# SparkX_smol_ARTIC_R2.net
KiCad netlist of a schematic drawn in EAGLE
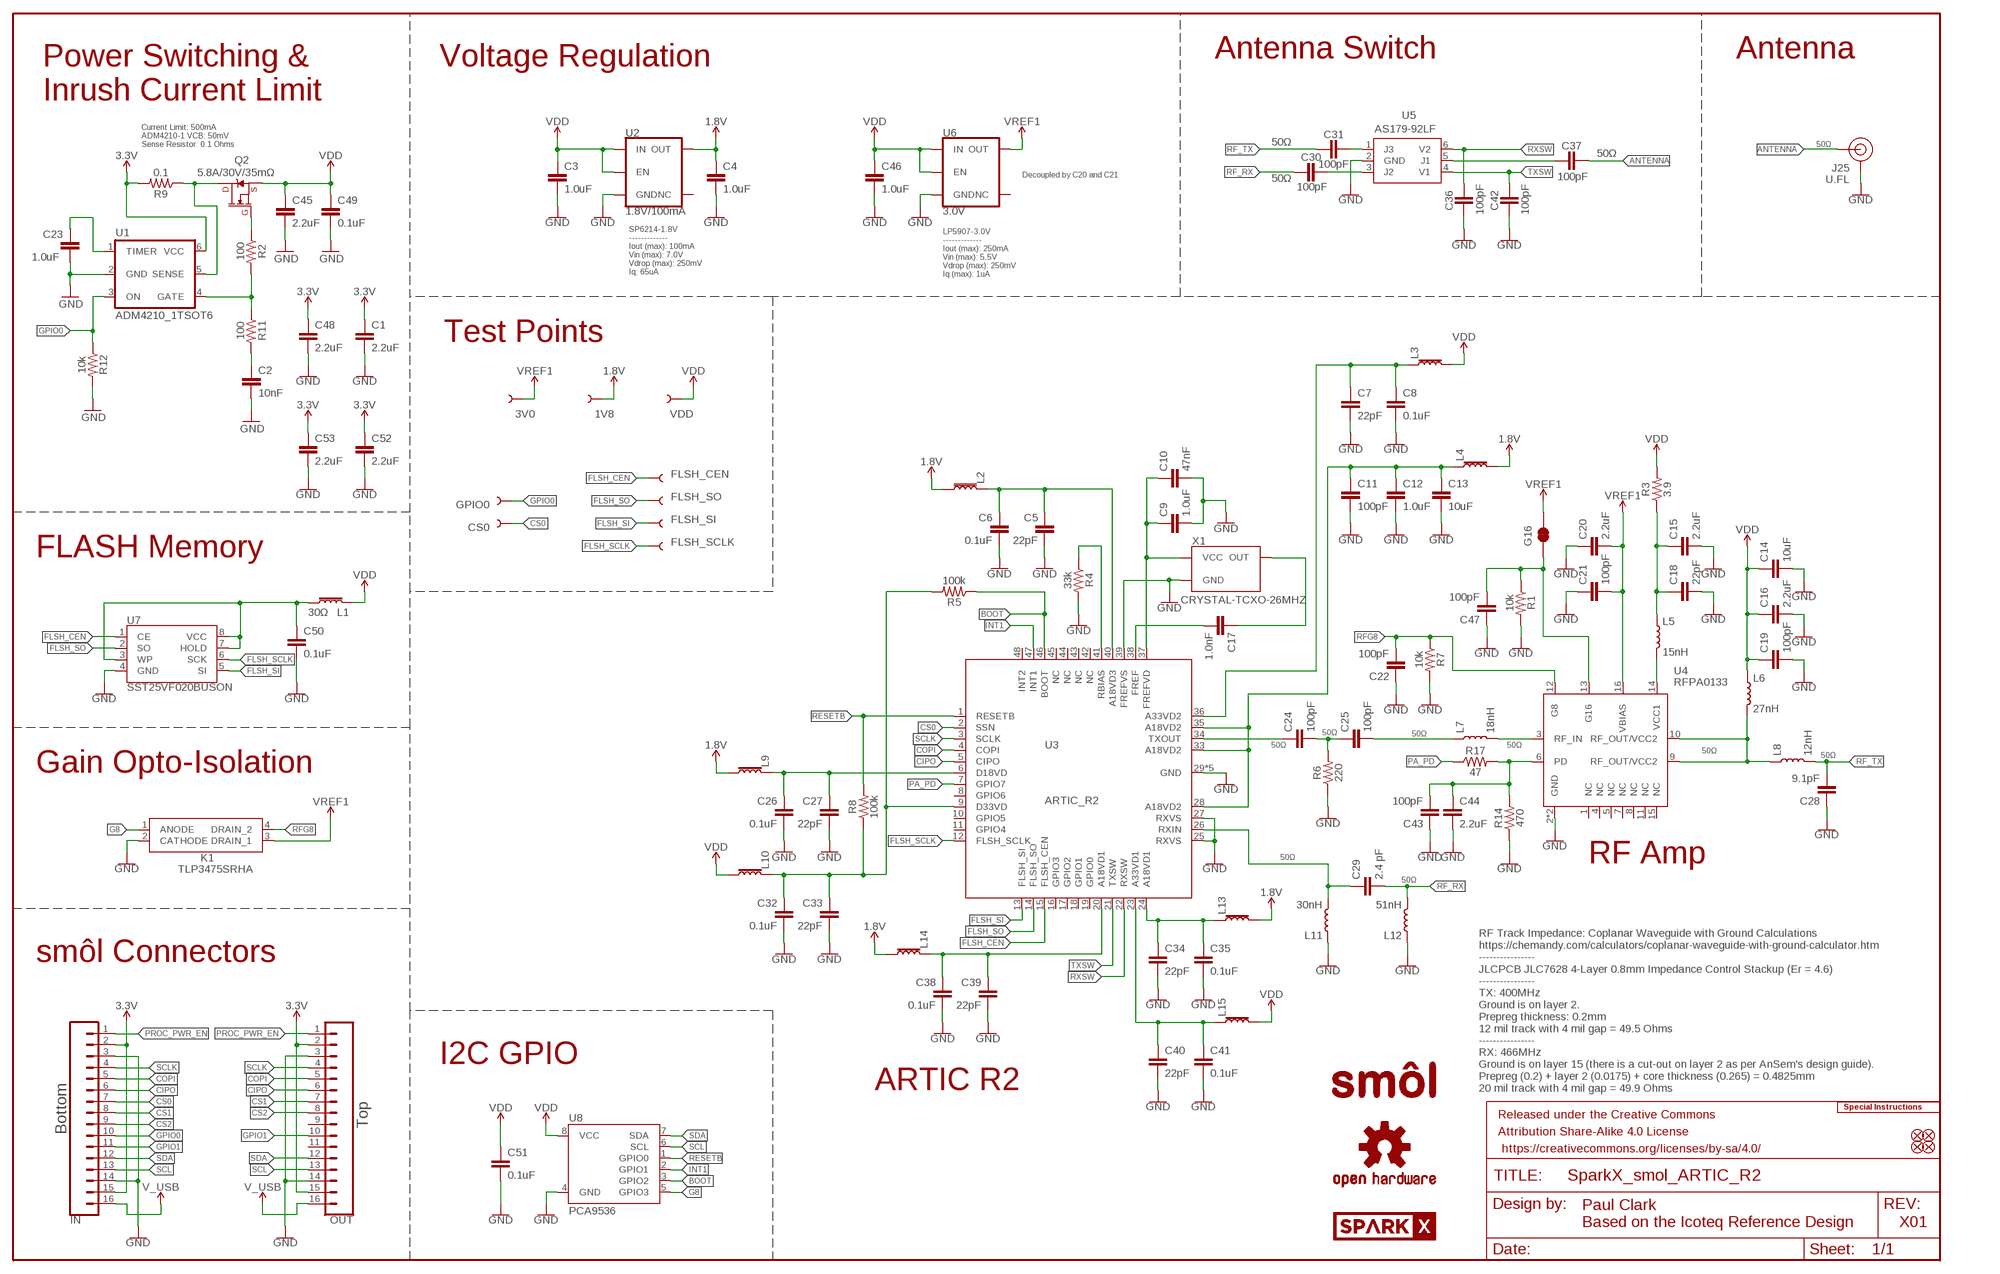
[diagram p0: schematic, sheet 1]

(export (version "E")
  (design (tool "Eeschema 10.0.6"))
  (components
    (comp (ref "1V8")
      (value "TEST-POINT3")
      (footprint "eagle-import:PAD.03X.03")
      (libsource (lib "eagle-import") (part "TEST-POINT3"))
    )
    (comp (ref "3V0")
      (value "TEST-POINT3")
      (footprint "eagle-import:PAD.03X.03")
      (libsource (lib "eagle-import") (part "TEST-POINT3"))
    )
    (comp (ref "C1")
      (value "2.2uF")
      (footprint "eagle-import:0402-TIGHT")
      (libsource (lib "eagle-import") (part "2.2UF-0402_TIGHT-10V-10%-X5R"))
    )
    (comp (ref "C2")
      (value "10nF")
      (footprint "eagle-import:0402-TIGHT")
      (libsource (lib "eagle-import") (part "10NF-0402T-25V-10%"))
    )
    (comp (ref "C3")
      (value "1.0uF")
      (footprint "eagle-import:0402-TIGHT")
      (libsource (lib "eagle-import") (part "1.0UF-0402T-16V-10%"))
    )
    (comp (ref "C4")
      (value "1.0uF")
      (footprint "eagle-import:0402-TIGHT")
      (libsource (lib "eagle-import") (part "1.0UF-0402T-16V-10%"))
    )
    (comp (ref "C5")
      (value "22pF")
      (footprint "eagle-import:0402-TIGHT")
      (libsource (lib "eagle-import") (part "22PF-0402T-16V-10%"))
    )
    (comp (ref "C6")
      (value "0.1uF")
      (footprint "eagle-import:0402-TIGHT")
      (libsource (lib "eagle-import") (part "0.1UF-0402T-6.3V-10%-X7R"))
    )
    (comp (ref "C7")
      (value "22pF")
      (footprint "eagle-import:0402-TIGHT")
      (libsource (lib "eagle-import") (part "22PF-0402T-16V-10%"))
    )
    (comp (ref "C8")
      (value "0.1uF")
      (footprint "eagle-import:0402-TIGHT")
      (libsource (lib "eagle-import") (part "0.1UF-0402T-6.3V-10%-X7R"))
    )
    (comp (ref "C9")
      (value "1.0uF")
      (footprint "eagle-import:0402-TIGHT")
      (libsource (lib "eagle-import") (part "1.0UF-0402T-16V-10%"))
    )
    (comp (ref "C10")
      (value "47nF")
      (footprint "eagle-import:0402-TIGHT")
      (libsource (lib "eagle-import") (part "47NF-0402_TIGHT-25V-10%-X7R"))
    )
    (comp (ref "C11")
      (value "100pF")
      (footprint "eagle-import:0402-TIGHT")
      (libsource (lib "eagle-import") (part "100PF-0402T-50V-5%"))
    )
    (comp (ref "C12")
      (value "1.0uF")
      (footprint "eagle-import:0402-TIGHT")
      (libsource (lib "eagle-import") (part "1.0UF-0402T-16V-10%"))
    )
    (comp (ref "C13")
      (value "10uF")
      (footprint "eagle-import:0402-TIGHT")
      (libsource (lib "eagle-import") (part "10UF-0402T-6.3V-20%"))
    )
    (comp (ref "C14")
      (value "10uF")
      (footprint "eagle-import:0402-TIGHT")
      (libsource (lib "eagle-import") (part "10UF-0402T-6.3V-20%"))
    )
    (comp (ref "C15")
      (value "2.2uF")
      (footprint "eagle-import:0402-TIGHT")
      (libsource (lib "eagle-import") (part "2.2UF-0402_TIGHT-10V-10%-X5R"))
    )
    (comp (ref "C16")
      (value "2.2uF")
      (footprint "eagle-import:0402-TIGHT")
      (libsource (lib "eagle-import") (part "2.2UF-0402_TIGHT-10V-10%-X5R"))
    )
    (comp (ref "C17")
      (value "1.0nF")
      (footprint "eagle-import:0402-TIGHT")
      (libsource (lib "eagle-import") (part "1.0NF/1000PF-0402_TIGHT-50V-10%"))
    )
    (comp (ref "C18")
      (value "22pF")
      (footprint "eagle-import:0402-TIGHT")
      (libsource (lib "eagle-import") (part "22PF-0402T-16V-10%"))
    )
    (comp (ref "C19")
      (value "100pF")
      (footprint "eagle-import:0402-TIGHT")
      (libsource (lib "eagle-import") (part "100PF-0402T-50V-5%"))
    )
    (comp (ref "C20")
      (value "2.2uF")
      (footprint "eagle-import:0402-TIGHT")
      (libsource (lib "eagle-import") (part "2.2UF-0402_TIGHT-10V-10%-X5R"))
    )
    (comp (ref "C21")
      (value "100pF")
      (footprint "eagle-import:0402-TIGHT")
      (libsource (lib "eagle-import") (part "100PF-0402T-50V-5%"))
    )
    (comp (ref "C22")
      (value "100pF")
      (footprint "eagle-import:0402-TIGHT")
      (libsource (lib "eagle-import") (part "100PF-0402T-50V-5%"))
    )
    (comp (ref "C23")
      (value "1.0uF")
      (footprint "eagle-import:0402-TIGHT")
      (libsource (lib "eagle-import") (part "1.0UF-0402T-16V-10%"))
    )
    (comp (ref "C24")
      (value "100pF")
      (footprint "eagle-import:0402-TIGHT")
      (libsource (lib "eagle-import") (part "100PF-0402T-50V-5%"))
    )
    (comp (ref "C25")
      (value "100pF")
      (footprint "eagle-import:0402-TIGHT")
      (libsource (lib "eagle-import") (part "100PF-0402T-50V-5%"))
    )
    (comp (ref "C26")
      (value "0.1uF")
      (footprint "eagle-import:0402-TIGHT")
      (libsource (lib "eagle-import") (part "0.1UF-0402T-6.3V-10%-X7R"))
    )
    (comp (ref "C27")
      (value "22pF")
      (footprint "eagle-import:0402-TIGHT")
      (libsource (lib "eagle-import") (part "22PF-0402T-16V-10%"))
    )
    (comp (ref "C28")
      (value "9.1pF")
      (footprint "eagle-import:0402-TIGHT")
      (fields (field (name "MOUSER_PART") "609-500R07S9R1CV4T"))
      (libsource (lib "eagle-import") (part "9.1PF-0402-TIGHT"))
    )
    (comp (ref "C29")
      (value "2.4 pF")
      (footprint "eagle-import:0402_MURATA")
      (libsource (lib "eagle-import") (part "2.4PF-0402"))
    )
    (comp (ref "C30")
      (value "100pF")
      (footprint "eagle-import:0402-TIGHT")
      (libsource (lib "eagle-import") (part "100PF-0402T-50V-5%"))
    )
    (comp (ref "C31")
      (value "100pF")
      (footprint "eagle-import:0402-TIGHT")
      (libsource (lib "eagle-import") (part "100PF-0402T-50V-5%"))
    )
    (comp (ref "C32")
      (value "0.1uF")
      (footprint "eagle-import:0402-TIGHT")
      (libsource (lib "eagle-import") (part "0.1UF-0402T-6.3V-10%-X7R"))
    )
    (comp (ref "C33")
      (value "22pF")
      (footprint "eagle-import:0402-TIGHT")
      (libsource (lib "eagle-import") (part "22PF-0402T-16V-10%"))
    )
    (comp (ref "C34")
      (value "22pF")
      (footprint "eagle-import:0402-TIGHT")
      (libsource (lib "eagle-import") (part "22PF-0402T-16V-10%"))
    )
    (comp (ref "C35")
      (value "0.1uF")
      (footprint "eagle-import:0402-TIGHT")
      (libsource (lib "eagle-import") (part "0.1UF-0402T-6.3V-10%-X7R"))
    )
    (comp (ref "C36")
      (value "100pF")
      (footprint "eagle-import:0402-TIGHT")
      (libsource (lib "eagle-import") (part "100PF-0402T-50V-5%"))
    )
    (comp (ref "C37")
      (value "100pF")
      (footprint "eagle-import:0402-TIGHT")
      (libsource (lib "eagle-import") (part "100PF-0402T-50V-5%"))
    )
    (comp (ref "C38")
      (value "0.1uF")
      (footprint "eagle-import:0402-TIGHT")
      (libsource (lib "eagle-import") (part "0.1UF-0402T-6.3V-10%-X7R"))
    )
    (comp (ref "C39")
      (value "22pF")
      (footprint "eagle-import:0402-TIGHT")
      (libsource (lib "eagle-import") (part "22PF-0402T-16V-10%"))
    )
    (comp (ref "C40")
      (value "22pF")
      (footprint "eagle-import:0402-TIGHT")
      (libsource (lib "eagle-import") (part "22PF-0402T-16V-10%"))
    )
    (comp (ref "C41")
      (value "0.1uF")
      (footprint "eagle-import:0402-TIGHT")
      (libsource (lib "eagle-import") (part "0.1UF-0402T-6.3V-10%-X7R"))
    )
    (comp (ref "C42")
      (value "100pF")
      (footprint "eagle-import:0402-TIGHT")
      (libsource (lib "eagle-import") (part "100PF-0402T-50V-5%"))
    )
    (comp (ref "C43")
      (value "100pF")
      (footprint "eagle-import:0402-TIGHT")
      (libsource (lib "eagle-import") (part "100PF-0402T-50V-5%"))
    )
    (comp (ref "C44")
      (value "2.2uF")
      (footprint "eagle-import:0402-TIGHT")
      (libsource (lib "eagle-import") (part "2.2UF-0402_TIGHT-10V-10%-X5R"))
    )
    (comp (ref "C45")
      (value "2.2uF")
      (footprint "eagle-import:0402-TIGHT")
      (libsource (lib "eagle-import") (part "2.2UF-0402_TIGHT-10V-10%-X5R"))
    )
    (comp (ref "C46")
      (value "1.0uF")
      (footprint "eagle-import:0402-TIGHT")
      (libsource (lib "eagle-import") (part "1.0UF-0402T-16V-10%"))
    )
    (comp (ref "C47")
      (value "100pF")
      (footprint "eagle-import:0402-TIGHT")
      (libsource (lib "eagle-import") (part "100PF-0402T-50V-5%"))
    )
    (comp (ref "C48")
      (value "2.2uF")
      (footprint "eagle-import:0402-TIGHT")
      (libsource (lib "eagle-import") (part "2.2UF-0402_TIGHT-10V-10%-X5R"))
    )
    (comp (ref "C49")
      (value "0.1uF")
      (footprint "eagle-import:0402-TIGHT")
      (libsource (lib "eagle-import") (part "0.1UF-0402T-10V-10%-X7R"))
    )
    (comp (ref "C50")
      (value "0.1uF")
      (footprint "eagle-import:0402-TIGHT")
      (libsource (lib "eagle-import") (part "0.1UF-0402T-6.3V-10%-X7R"))
    )
    (comp (ref "C51")
      (value "0.1uF")
      (footprint "eagle-import:0402-TIGHT")
      (libsource (lib "eagle-import") (part "0.1UF-0402T-10V-10%-X7R"))
    )
    (comp (ref "C52")
      (value "2.2uF")
      (footprint "eagle-import:0402-TIGHT")
      (libsource (lib "eagle-import") (part "2.2UF-0402_TIGHT-10V-10%-X5R"))
    )
    (comp (ref "C53")
      (value "2.2uF")
      (footprint "eagle-import:0402-TIGHT")
      (libsource (lib "eagle-import") (part "2.2UF-0402_TIGHT-10V-10%-X5R"))
    )
    (comp (ref "CS0")
      (value "TEST-POINT3")
      (footprint "eagle-import:PAD.03X.03")
      (libsource (lib "eagle-import") (part "TEST-POINT3"))
    )
    (comp (ref "FD1")
      (value "FIDUCIALUFIDUCIAL")
      (footprint "eagle-import:FIDUCIAL-MICRO")
      (libsource (lib "eagle-import") (part "FIDUCIALUFIDUCIAL"))
    )
    (comp (ref "FD2")
      (value "FIDUCIALUFIDUCIAL")
      (footprint "eagle-import:FIDUCIAL-MICRO")
      (libsource (lib "eagle-import") (part "FIDUCIALUFIDUCIAL"))
    )
    (comp (ref "FD3")
      (value "FIDUCIALUFIDUCIAL")
      (footprint "eagle-import:FIDUCIAL-MICRO")
      (libsource (lib "eagle-import") (part "FIDUCIALUFIDUCIAL"))
    )
    (comp (ref "FD4")
      (value "FIDUCIALUFIDUCIAL")
      (footprint "eagle-import:FIDUCIAL-MICRO")
      (libsource (lib "eagle-import") (part "FIDUCIALUFIDUCIAL"))
    )
    (comp (ref "FLSH_CEN")
      (value "TEST-POINT3")
      (footprint "eagle-import:PAD.03X.03")
      (libsource (lib "eagle-import") (part "TEST-POINT3"))
    )
    (comp (ref "FLSH_SCLK")
      (value "TEST-POINT3")
      (footprint "eagle-import:PAD.03X.03")
      (libsource (lib "eagle-import") (part "TEST-POINT3"))
    )
    (comp (ref "FLSH_SI")
      (value "TEST-POINT3")
      (footprint "eagle-import:PAD.03X.03")
      (libsource (lib "eagle-import") (part "TEST-POINT3"))
    )
    (comp (ref "FLSH_SO")
      (value "TEST-POINT3")
      (footprint "eagle-import:PAD.03X.03")
      (libsource (lib "eagle-import") (part "TEST-POINT3"))
    )
    (comp (ref "FRAME1")
      (value "FRAME-LEDGER")
      (footprint "eagle-import:CREATIVE_COMMONS")
      (libsource (lib "eagle-import") (part "FRAME-LEDGER"))
    )
    (comp (ref "G16")
      (value "JUMPER-SMT_2_NC_TRACE_NO-SILK")
      (footprint "eagle-import:SMT-JUMPER_2_NC_TRACE_NO-SILK")
      (libsource (lib "eagle-import") (part "JUMPER-SMT_2_NC_TRACE_NO-SILK"))
    )
    (comp (ref "GPIO0")
      (value "TEST-POINT3")
      (footprint "eagle-import:PAD.03X.03")
      (libsource (lib "eagle-import") (part "TEST-POINT3"))
    )
    (comp (ref "IN")
      (value "CONN_16FPC_16_0.5MM")
      (footprint "eagle-import:FPC_16_0.5MM")
      (libsource (lib "eagle-import") (part "CONN_16FPC_16_0.5MM"))
    )
    (comp (ref "J25")
      (value "U.FL")
      (footprint "eagle-import:U.FL_REDUCED_FOOTPRINT")
      (libsource (lib "eagle-import") (part "U.FL2PIN-REDUCED-FOOTPRINT"))
    )
    (comp (ref "K1")
      (value "TLP3475SRHA")
      (footprint "eagle-import:TLP3475SRHA")
      (fields (field (name "DIGIKEY_PART") "264-TLP3475SRHA(TPECT-ND - Cut Tape (CT)"))
      (libsource (lib "eagle-import") (part "TLP3475SRHA"))
    )
    (comp (ref "L1")
      (value "30Ω")
      (footprint "eagle-import:0402-TIGHT")
      (libsource (lib "eagle-import") (part "FERRITE_BEAD-0402-30Ω-100MHZ"))
    )
    (comp (ref "L2")
      (value "30Ω")
      (footprint "eagle-import:0402-TIGHT")
      (libsource (lib "eagle-import") (part "FERRITE_BEAD-0402-30Ω-100MHZ"))
    )
    (comp (ref "L3")
      (value "30Ω")
      (footprint "eagle-import:0402-TIGHT")
      (libsource (lib "eagle-import") (part "FERRITE_BEAD-0402-30Ω-100MHZ"))
    )
    (comp (ref "L4")
      (value "30Ω")
      (footprint "eagle-import:0402-TIGHT")
      (libsource (lib "eagle-import") (part "FERRITE_BEAD-0402-30Ω-100MHZ"))
    )
    (comp (ref "L5")
      (value "15nH")
      (footprint "eagle-import:0402_COILCRAFT")
      (fields (field (name "MOUSER_PART") "994-0402HP-15NXGLU"))
      (libsource (lib "eagle-import") (part "15NH-0402"))
    )
    (comp (ref "L6")
      (value "27nH")
      (footprint "eagle-import:0402_COILCRAFT")
      (fields (field (name "MOUSER_PART") "994-0402HP-27NXGLU"))
      (libsource (lib "eagle-import") (part "27NH-0402"))
    )
    (comp (ref "L7")
      (value "18nH")
      (footprint "eagle-import:0402_COILCRAFT")
      (fields (field (name "MOUSER_PART") "994-0402HP-18NXGLU"))
      (libsource (lib "eagle-import") (part "18NH-0402"))
    )
    (comp (ref "L8")
      (value "12nH")
      (footprint "eagle-import:0402_COILCRAFT")
      (fields (field (name "MOUSER_PART") "994-0402HP-12NXGLU"))
      (libsource (lib "eagle-import") (part "12NH-0402"))
    )
    (comp (ref "L9")
      (value "30Ω")
      (footprint "eagle-import:0402-TIGHT")
      (libsource (lib "eagle-import") (part "FERRITE_BEAD-0402-30Ω-100MHZ"))
    )
    (comp (ref "L10")
      (value "30Ω")
      (footprint "eagle-import:0402-TIGHT")
      (libsource (lib "eagle-import") (part "FERRITE_BEAD-0402-30Ω-100MHZ"))
    )
    (comp (ref "L11")
      (value "30nH")
      (footprint "eagle-import:0402_COILCRAFT")
      (fields (field (name "MOUSER_PART") "994-0402HP-30NXGLU"))
      (libsource (lib "eagle-import") (part "30NH-0402"))
    )
    (comp (ref "L12")
      (value "51nH")
      (footprint "eagle-import:0402_COILCRAFT")
      (fields (field (name "MOUSER_PART") "994-0402HP-51NXGLU"))
      (libsource (lib "eagle-import") (part "51NH-0402"))
    )
    (comp (ref "L13")
      (value "30Ω")
      (footprint "eagle-import:0402-TIGHT")
      (libsource (lib "eagle-import") (part "FERRITE_BEAD-0402-30Ω-100MHZ"))
    )
    (comp (ref "L14")
      (value "30Ω")
      (footprint "eagle-import:0402-TIGHT")
      (libsource (lib "eagle-import") (part "FERRITE_BEAD-0402-30Ω-100MHZ"))
    )
    (comp (ref "L15")
      (value "30Ω")
      (footprint "eagle-import:0402-TIGHT")
      (libsource (lib "eagle-import") (part "FERRITE_BEAD-0402-30Ω-100MHZ"))
    )
    (comp (ref "LOGO1")
      (value "SPECIAL_INSTRUCTIONS-ORDERING")
      (footprint "eagle-import:ORDERING_INSTRUCTIONS")
      (libsource (lib "eagle-import") (part "SPECIAL_INSTRUCTIONS-ORDERING"))
    )
    (comp (ref "LOGO2")
      (value "OSHW-LOGOMINI")
      (footprint "eagle-import:OSHW-LOGO-MINI")
      (libsource (lib "eagle-import") (part "OSHW-LOGOMINI"))
    )
    (comp (ref "LOGO3")
      (value "OSHW-LOGOMINI")
      (footprint "eagle-import:OSHW-LOGO-MINI")
      (libsource (lib "eagle-import") (part "OSHW-LOGOMINI"))
    )
    (comp (ref "OUT")
      (value "CONN_16FPC_16_0.5MM")
      (footprint "eagle-import:FPC_16_0.5MM")
      (libsource (lib "eagle-import") (part "CONN_16FPC_16_0.5MM"))
    )
    (comp (ref "Q2")
      (value "5.8A/30V/35mΩ")
      (footprint "eagle-import:SOT23-3")
      (libsource (lib "eagle-import") (part "MOSFET-NCH-AO3404A"))
    )
    (comp (ref "R1")
      (value "10k")
      (footprint "eagle-import:0402-TIGHT")
      (libsource (lib "eagle-import") (part "10KOHM-0402T-1/16W-1%"))
    )
    (comp (ref "R2")
      (value "100")
      (footprint "eagle-import:0402-TIGHT")
      (libsource (lib "eagle-import") (part "100OHM-0402-TIGHT-1/16W-1%"))
    )
    (comp (ref "R3")
      (value "3.9")
      (footprint "eagle-import:0402-TIGHT")
      (libsource (lib "eagle-import") (part "3.9OHM-0402-TIGHT-1/16W-1%"))
    )
    (comp (ref "R4")
      (value "33k")
      (footprint "eagle-import:0402-TIGHT")
      (libsource (lib "eagle-import") (part "33KOHM-0402T-1/16W-1%"))
    )
    (comp (ref "R5")
      (value "100k")
      (footprint "eagle-import:0402-TIGHT")
      (libsource (lib "eagle-import") (part "100KOHM-0402T-1/16W-1%"))
    )
    (comp (ref "R6")
      (value "220")
      (footprint "eagle-import:0402-TIGHT")
      (libsource (lib "eagle-import") (part "220OHM-0402-TIGHT-1/16W-1%"))
    )
    (comp (ref "R7")
      (value "10k")
      (footprint "eagle-import:0402-TIGHT")
      (libsource (lib "eagle-import") (part "10KOHM-0402T-1/16W-1%"))
    )
    (comp (ref "R8")
      (value "100k")
      (footprint "eagle-import:0402-TIGHT")
      (libsource (lib "eagle-import") (part "100KOHM-0402T-1/16W-1%"))
    )
    (comp (ref "R9")
      (value "0.1")
      (footprint "eagle-import:0603")
      (libsource (lib "eagle-import") (part "0.1OHM-0603-1/3W-1%"))
    )
    (comp (ref "R11")
      (value "100")
      (footprint "eagle-import:0402-TIGHT")
      (libsource (lib "eagle-import") (part "100OHM-0402-TIGHT-1/16W-1%"))
    )
    (comp (ref "R12")
      (value "10k")
      (footprint "eagle-import:0402-TIGHT")
      (libsource (lib "eagle-import") (part "10KOHM-0402T-1/16W-1%"))
    )
    (comp (ref "R14")
      (value "470")
      (footprint "eagle-import:0402-TIGHT")
      (libsource (lib "eagle-import") (part "470OHM-0402-TIGHT-1/16W-1%"))
    )
    (comp (ref "R17")
      (value "47")
      (footprint "eagle-import:0402-TIGHT")
      (libsource (lib "eagle-import") (part "47OHM-0402-TIGHT-1/16W-1%"))
    )
    (comp (ref "U$2")
      (value "SMOL_LOGOSMALL")
      (footprint "eagle-import:SMOL_SMALL")
      (libsource (lib "eagle-import") (part "SMOL_LOGOSMALL"))
    )
    (comp (ref "U$3")
      (value "SMOL_LOGOSMALL")
      (footprint "eagle-import:SMOL_SMALL")
      (libsource (lib "eagle-import") (part "SMOL_LOGOSMALL"))
    )
    (comp (ref "U$4")
      (value "SPARKX-LOGO3")
      (footprint "eagle-import:SPARKX-SMALL")
      (libsource (lib "eagle-import") (part "SPARKX-LOGO3"))
    )
    (comp (ref "U$8")
      (value "SPARKX-LOGO2")
      (footprint "eagle-import:SPARKX-TINY")
      (libsource (lib "eagle-import") (part "SPARKX-LOGO2"))
    )
    (comp (ref "U1")
      (value "ADM4210_1TSOT6")
      (footprint "eagle-import:TSOT6")
      (libsource (lib "eagle-import") (part "ADM4210_1TSOT6"))
    )
    (comp (ref "U2")
      (value "1.8V/100mA")
      (footprint "eagle-import:SC70")
      (libsource (lib "eagle-import") (part "V_REG_SP6214-1.8V"))
    )
    (comp (ref "U3")
      (value "ARTIC_R2")
      (footprint "eagle-import:QFN-48")
      (libsource (lib "eagle-import") (part "ARTIC_R2"))
    )
    (comp (ref "U4")
      (value "RFPA0133")
      (footprint "eagle-import:QFN50P300X300X86-17N")
      (fields
        (field (name "MANUFACTURER_PART_NUMBER") "RFPA0133TR7")
        (field (name "MOUSER_PART_NUMBER") "772-RFPA0133")
      )
      (libsource (lib "eagle-import") (part "RFPA0133"))
    )
    (comp (ref "U5")
      (value "AS179-92LF")
      (footprint "eagle-import:SOT65P220X100-6N")
      (libsource (lib "eagle-import") (part "AS179-92LF"))
    )
    (comp (ref "U6")
      (value "3.0V")
      (footprint "eagle-import:SOT23-5")
      (fields
        (field (name "DIGIKEY_PART") "296-40357-1-ND")
        (field (name "MANU_PART") "LP5907MFX-3.0/NOPB")
        (field (name "MOUSER_PART") "595-LP5907MFX-3.0NPB")
      )
      (libsource (lib "eagle-import") (part "V_REG_LP5907SOT23-3.0V"))
    )
    (comp (ref "U7")
      (value "SST25VF020BUSON")
      (footprint "eagle-import:USON_3X2MM")
      (fields
        (field (name "DIGIKEY_PART") "SST25VF020B-80-4I-Q3AE-TCT-ND")
        (field (name "MANU_PART") "SST25VF020B-80-4I-Q3AE-T")
      )
      (libsource (lib "eagle-import") (part "SST25VF020BUSON"))
    )
    (comp (ref "U8")
      (value "PCA9536")
      (footprint "eagle-import:MSOP8")
      (libsource (lib "eagle-import") (part "PCA9536"))
    )
    (comp (ref "VDD")
      (value "TEST-POINT3")
      (footprint "eagle-import:PAD.03X.03")
      (libsource (lib "eagle-import") (part "TEST-POINT3"))
    )
    (comp (ref "X1")
      (value "CRYSTAL-TCXO-26MHZ")
      (footprint "eagle-import:CRYSTAL-TCXO-SMD-1.65X1.25")
      (fields (field (name "MOUSER_PART") "449-LFTCXO073004CUTT"))
      (libsource (lib "eagle-import") (part "CRYSTAL-TCXO-26MHZ"))
    )
  )
  (nets
    (net (code "1") (name "1.8V") (class "Default")
      (node (ref "1V8") (pin "1") (pinfunction "1_1") (pintype "bidirectional"))
      (node (ref "C4") (pin "1") (pinfunction "1_1") (pintype "passive"))
      (node (ref "L13") (pin "2") (pinfunction "2_2") (pintype "passive"))
      (node (ref "L14") (pin "2") (pinfunction "2_2") (pintype "passive"))
      (node (ref "L2") (pin "2") (pinfunction "2_2") (pintype "passive"))
      (node (ref "L4") (pin "2") (pinfunction "2_2") (pintype "passive"))
      (node (ref "L9") (pin "2") (pinfunction "2_2") (pintype "passive"))
      (node (ref "U2") (pin "5") (pinfunction "OUT_5") (pintype "passive"))
    )
    (net (code "2") (name "3.3V") (class "Default")
      (node (ref "C1") (pin "1") (pinfunction "1_1") (pintype "passive"))
      (node (ref "C48") (pin "1") (pinfunction "1_1") (pintype "passive"))
      (node (ref "C52") (pin "1") (pinfunction "1_1") (pintype "passive"))
      (node (ref "C53") (pin "1") (pinfunction "1_1") (pintype "passive"))
      (node (ref "IN") (pin "15") (pinfunction "15_15") (pintype "passive"))
      (node (ref "IN") (pin "2") (pinfunction "2_2") (pintype "passive"))
      (node (ref "OUT") (pin "15") (pinfunction "15_15") (pintype "passive"))
      (node (ref "OUT") (pin "2") (pinfunction "2_2") (pintype "passive"))
      (node (ref "R9") (pin "2") (pinfunction "2_2") (pintype "passive"))
      (node (ref "U1") (pin "6") (pinfunction "VCC_6") (pintype "power_in"))
    )
    (net (code "3") (name "ANTENNA") (class "Default")
      (node (ref "C37") (pin "1") (pinfunction "1_1") (pintype "passive"))
      (node (ref "J25") (pin "FEED") (pinfunction "SIGNAL_FEED") (pintype "bidirectional"))
    )
    (net (code "4") (name "BOOT") (class "Default")
      (node (ref "R5") (pin "1") (pinfunction "1_1") (pintype "passive"))
      (node (ref "U3") (pin "46") (pinfunction "BOOT_46") (pintype "bidirectional"))
      (node (ref "U8") (pin "3") (pinfunction "GPIO2_3") (pintype "bidirectional"))
    )
    (net (code "5") (name "CIPO") (class "Default")
      (node (ref "IN") (pin "6") (pinfunction "6_6") (pintype "passive"))
      (node (ref "OUT") (pin "6") (pinfunction "6_6") (pintype "passive"))
      (node (ref "U3") (pin "5") (pinfunction "CIPO_5") (pintype "bidirectional"))
    )
    (net (code "6") (name "COPI") (class "Default")
      (node (ref "IN") (pin "5") (pinfunction "5_5") (pintype "passive"))
      (node (ref "OUT") (pin "5") (pinfunction "5_5") (pintype "passive"))
      (node (ref "U3") (pin "4") (pinfunction "COPI_4") (pintype "bidirectional"))
    )
    (net (code "7") (name "CS0") (class "Default")
      (node (ref "CS0") (pin "1") (pinfunction "1_1") (pintype "bidirectional"))
      (node (ref "IN") (pin "7") (pinfunction "7_7") (pintype "passive"))
      (node (ref "U3") (pin "2") (pinfunction "SSN_2") (pintype "bidirectional"))
    )
    (net (code "8") (name "CS1") (class "Default")
      (node (ref "IN") (pin "8") (pinfunction "8_8") (pintype "passive"))
      (node (ref "OUT") (pin "7") (pinfunction "7_7") (pintype "passive"))
    )
    (net (code "9") (name "CS2") (class "Default")
      (node (ref "IN") (pin "9") (pinfunction "9_9") (pintype "passive"))
      (node (ref "OUT") (pin "8") (pinfunction "8_8") (pintype "passive"))
    )
    (net (code "10") (name "FLSH_CEN") (class "Default")
      (node (ref "FLSH_CEN") (pin "1") (pinfunction "1_1") (pintype "bidirectional"))
      (node (ref "U3") (pin "15") (pinfunction "FLSH_CEN_15") (pintype "bidirectional"))
      (node (ref "U7") (pin "1") (pinfunction "CE_1") (pintype "bidirectional"))
    )
    (net (code "11") (name "FLSH_SCLK") (class "Default")
      (node (ref "FLSH_SCLK") (pin "1") (pinfunction "1_1") (pintype "bidirectional"))
      (node (ref "U3") (pin "12") (pinfunction "FLSH_SCLK_12") (pintype "bidirectional"))
      (node (ref "U7") (pin "6") (pinfunction "SCK_6") (pintype "bidirectional"))
    )
    (net (code "12") (name "FLSH_SI") (class "Default")
      (node (ref "FLSH_SI") (pin "1") (pinfunction "1_1") (pintype "bidirectional"))
      (node (ref "U3") (pin "13") (pinfunction "FLSH_SI_13") (pintype "bidirectional"))
      (node (ref "U7") (pin "5") (pinfunction "SI_5") (pintype "bidirectional"))
    )
    (net (code "13") (name "FLSH_SO") (class "Default")
      (node (ref "FLSH_SO") (pin "1") (pinfunction "1_1") (pintype "bidirectional"))
      (node (ref "U3") (pin "14") (pinfunction "FLSH_SO_14") (pintype "bidirectional"))
      (node (ref "U7") (pin "2") (pinfunction "SO_2") (pintype "bidirectional"))
    )
    (net (code "14") (name "G8") (class "Default")
      (node (ref "K1") (pin "1") (pinfunction "ANODE_1") (pintype "bidirectional"))
      (node (ref "U8") (pin "5") (pinfunction "GPIO3_5") (pintype "bidirectional"))
    )
    (net (code "15") (name "GND") (class "Default")
      (node (ref "C1") (pin "2") (pinfunction "2_2") (pintype "passive"))
      (node (ref "C10") (pin "2") (pinfunction "2_2") (pintype "passive"))
      (node (ref "C11") (pin "2") (pinfunction "2_2") (pintype "passive"))
      (node (ref "C12") (pin "2") (pinfunction "2_2") (pintype "passive"))
      (node (ref "C13") (pin "2") (pinfunction "2_2") (pintype "passive"))
      (node (ref "C14") (pin "2") (pinfunction "2_2") (pintype "passive"))
      (node (ref "C15") (pin "2") (pinfunction "2_2") (pintype "passive"))
      (node (ref "C16") (pin "2") (pinfunction "2_2") (pintype "passive"))
      (node (ref "C18") (pin "2") (pinfunction "2_2") (pintype "passive"))
      (node (ref "C19") (pin "2") (pinfunction "2_2") (pintype "passive"))
      (node (ref "C2") (pin "2") (pinfunction "2_2") (pintype "passive"))
      (node (ref "C20") (pin "1") (pinfunction "1_1") (pintype "passive"))
      (node (ref "C21") (pin "1") (pinfunction "1_1") (pintype "passive"))
      (node (ref "C22") (pin "1") (pinfunction "1_1") (pintype "passive"))
      (node (ref "C23") (pin "2") (pinfunction "2_2") (pintype "passive"))
      (node (ref "C26") (pin "2") (pinfunction "2_2") (pintype "passive"))
      (node (ref "C27") (pin "2") (pinfunction "2_2") (pintype "passive"))
      (node (ref "C28") (pin "1") (pinfunction "1_1") (pintype "passive"))
      (node (ref "C3") (pin "2") (pinfunction "2_2") (pintype "passive"))
      (node (ref "C32") (pin "2") (pinfunction "2_2") (pintype "passive"))
      (node (ref "C33") (pin "2") (pinfunction "2_2") (pintype "passive"))
      (node (ref "C34") (pin "2") (pinfunction "2_2") (pintype "passive"))
      (node (ref "C35") (pin "2") (pinfunction "2_2") (pintype "passive"))
      (node (ref "C36") (pin "2") (pinfunction "2_2") (pintype "passive"))
      (node (ref "C38") (pin "2") (pinfunction "2_2") (pintype "passive"))
      (node (ref "C39") (pin "2") (pinfunction "2_2") (pintype "passive"))
      (node (ref "C4") (pin "2") (pinfunction "2_2") (pintype "passive"))
      (node (ref "C40") (pin "2") (pinfunction "2_2") (pintype "passive"))
      (node (ref "C41") (pin "2") (pinfunction "2_2") (pintype "passive"))
      (node (ref "C42") (pin "2") (pinfunction "2_2") (pintype "passive"))
      (node (ref "C43") (pin "1") (pinfunction "1_1") (pintype "passive"))
      (node (ref "C44") (pin "2") (pinfunction "2_2") (pintype "passive"))
      (node (ref "C45") (pin "2") (pinfunction "2_2") (pintype "passive"))
      (node (ref "C46") (pin "2") (pinfunction "2_2") (pintype "passive"))
      (node (ref "C47") (pin "1") (pinfunction "1_1") (pintype "passive"))
      (node (ref "C48") (pin "2") (pinfunction "2_2") (pintype "passive"))
      (node (ref "C49") (pin "2") (pinfunction "2_2") (pintype "passive"))
      (node (ref "C5") (pin "2") (pinfunction "2_2") (pintype "passive"))
      (node (ref "C50") (pin "2") (pinfunction "2_2") (pintype "passive"))
      (node (ref "C51") (pin "2") (pinfunction "2_2") (pintype "passive"))
      (node (ref "C52") (pin "2") (pinfunction "2_2") (pintype "passive"))
      (node (ref "C53") (pin "2") (pinfunction "2_2") (pintype "passive"))
      (node (ref "C6") (pin "2") (pinfunction "2_2") (pintype "passive"))
      (node (ref "C7") (pin "2") (pinfunction "2_2") (pintype "passive"))
      (node (ref "C8") (pin "2") (pinfunction "2_2") (pintype "passive"))
      (node (ref "C9") (pin "2") (pinfunction "2_2") (pintype "passive"))
      (node (ref "IN") (pin "14") (pinfunction "14_14") (pintype "passive"))
      (node (ref "IN") (pin "3") (pinfunction "3_3") (pintype "passive"))
      (node (ref "J25") (pin "1") (pinfunction "GND_1") (pintype "bidirectional"))
      (node (ref "J25") (pin "2") (pinfunction "GND_2") (pintype "bidirectional"))
      (node (ref "K1") (pin "2") (pinfunction "CATHODE_2") (pintype "bidirectional"))
      (node (ref "L11") (pin "P$1") (pinfunction "1_P$1") (pintype "passive"))
      (node (ref "L12") (pin "P$1") (pinfunction "1_P$1") (pintype "passive"))
      (node (ref "OUT") (pin "14") (pinfunction "14_14") (pintype "passive"))
      (node (ref "OUT") (pin "3") (pinfunction "3_3") (pintype "passive"))
      (node (ref "R1") (pin "2") (pinfunction "2_2") (pintype "passive"))
      (node (ref "R12") (pin "2") (pinfunction "2_2") (pintype "passive"))
      (node (ref "R14") (pin "1") (pinfunction "1_1") (pintype "passive"))
      (node (ref "R4") (pin "2") (pinfunction "2_2") (pintype "passive"))
      (node (ref "R6") (pin "1") (pinfunction "1_1") (pintype "passive"))
      (node (ref "R7") (pin "2") (pinfunction "2_2") (pintype "passive"))
      (node (ref "U1") (pin "2") (pinfunction "GND_2") (pintype "power_in"))
      (node (ref "U2") (pin "2") (pinfunction "GND_2") (pintype "input"))
      (node (ref "U3") (pin "25") (pinfunction "RXVS_25") (pintype "bidirectional"))
      (node (ref "U3") (pin "27") (pinfunction "RXVS_27") (pintype "bidirectional"))
      (node (ref "U3") (pin "29") (pinfunction "GND_29") (pintype "bidirectional"))
      (node (ref "U3") (pin "30") (pinfunction "GND_30") (pintype "bidirectional"))
      (node (ref "U3") (pin "31") (pinfunction "GND_31") (pintype "bidirectional"))
      (node (ref "U3") (pin "32") (pinfunction "GND_32") (pintype "bidirectional"))
      (node (ref "U3") (pin "39") (pinfunction "FREFVS_39") (pintype "bidirectional"))
      (node (ref "U3") (pin "GND") (pinfunction "GND_GND") (pintype "bidirectional"))
      (node (ref "U4") (pin "2") (pinfunction "GND_2") (pintype "power_in"))
      (node (ref "U4") (pin "EDAP") (pinfunction "GND_EDAP") (pintype "power_in"))
      (node (ref "U5") (pin "2") (pinfunction "GND_2") (pintype "power_in"))
      (node (ref "U6") (pin "2") (pinfunction "GND_2") (pintype "input"))
      (node (ref "U7") (pin "4") (pinfunction "GND_4") (pintype "power_in"))
      (node (ref "U8") (pin "4") (pinfunction "GND_4") (pintype "bidirectional"))
      (node (ref "X1") (pin "1") (pinfunction "GND_1") (pintype "bidirectional"))
      (node (ref "X1") (pin "2") (pinfunction "GND_2") (pintype "bidirectional"))
    )
    (net (code "16") (name "GPIO0") (class "Default")
      (node (ref "GPIO0") (pin "1") (pinfunction "1_1") (pintype "bidirectional"))
      (node (ref "IN") (pin "10") (pinfunction "10_10") (pintype "passive"))
      (node (ref "R12") (pin "1") (pinfunction "1_1") (pintype "passive"))
      (node (ref "U1") (pin "3") (pinfunction "ON_3") (pintype "input"))
    )
    (net (code "17") (name "GPIO1") (class "Default")
      (node (ref "IN") (pin "11") (pinfunction "11_11") (pintype "passive"))
      (node (ref "OUT") (pin "10") (pinfunction "10_10") (pintype "passive"))
    )
    (net (code "18") (name "INT1") (class "Default")
      (node (ref "U3") (pin "47") (pinfunction "INT1_47") (pintype "bidirectional"))
      (node (ref "U8") (pin "2") (pinfunction "GPIO1_2") (pintype "bidirectional"))
    )
    (net (code "19") (name "Net-(C2-Pad1)") (class "Default")
      (node (ref "C2") (pin "1") (pinfunction "1_1") (pintype "passive"))
      (node (ref "R11") (pin "2") (pinfunction "2_2") (pintype "passive"))
    )
    (net (code "20") (name "Net-(C11-Pad1)") (class "Default")
      (node (ref "C11") (pin "1") (pinfunction "1_1") (pintype "passive"))
      (node (ref "C12") (pin "1") (pinfunction "1_1") (pintype "passive"))
      (node (ref "C13") (pin "1") (pinfunction "1_1") (pintype "passive"))
      (node (ref "L4") (pin "1") (pinfunction "1_1") (pintype "passive"))
      (node (ref "U3") (pin "28") (pinfunction "A18VD2_28") (pintype "power_in"))
      (node (ref "U3") (pin "33") (pinfunction "A18VD2_33") (pintype "power_in"))
      (node (ref "U3") (pin "35") (pinfunction "A18VD2_35") (pintype "power_in"))
    )
    (net (code "21") (name "Net-(C24-Pad2)") (class "Default")
      (node (ref "C24") (pin "2") (pinfunction "2_2") (pintype "passive"))
      (node (ref "C25") (pin "1") (pinfunction "1_1") (pintype "passive"))
      (node (ref "R6") (pin "2") (pinfunction "2_2") (pintype "passive"))
    )
    (net (code "22") (name "Net-(C29-1)") (class "Default")
      (node (ref "C29") (pin "P$1") (pinfunction "1_P$1") (pintype "passive"))
      (node (ref "L11") (pin "P$2") (pinfunction "2_P$2") (pintype "passive"))
      (node (ref "U3") (pin "26") (pinfunction "RXIN_26") (pintype "bidirectional"))
    )
    (net (code "23") (name "Net-(C34-Pad1)") (class "Default")
      (node (ref "C34") (pin "1") (pinfunction "1_1") (pintype "passive"))
      (node (ref "C35") (pin "1") (pinfunction "1_1") (pintype "passive"))
      (node (ref "L13") (pin "1") (pinfunction "1_1") (pintype "passive"))
      (node (ref "U3") (pin "24") (pinfunction "A18VD1_24") (pintype "power_in"))
    )
    (net (code "24") (name "Net-(C38-Pad1)") (class "Default")
      (node (ref "C38") (pin "1") (pinfunction "1_1") (pintype "passive"))
      (node (ref "C39") (pin "1") (pinfunction "1_1") (pintype "passive"))
      (node (ref "L14") (pin "1") (pinfunction "1_1") (pintype "passive"))
      (node (ref "U3") (pin "20") (pinfunction "A18VD1_20") (pintype "power_in"))
    )
    (net (code "25") (name "Net-(L5-1)") (class "Default")
      (node (ref "C15") (pin "1") (pinfunction "1_1") (pintype "passive"))
      (node (ref "C18") (pin "1") (pinfunction "1_1") (pintype "passive"))
      (node (ref "L5") (pin "P$1") (pinfunction "1_P$1") (pintype "passive"))
      (node (ref "R3") (pin "1") (pinfunction "1_1") (pintype "passive"))
    )
    (net (code "26") (name "Net-(L5-2)") (class "Default")
      (node (ref "L5") (pin "P$2") (pinfunction "2_P$2") (pintype "passive"))
      (node (ref "U4") (pin "14") (pinfunction "VCC1_14") (pintype "power_in"))
    )
    (net (code "27") (name "Net-(L6-2)") (class "Default")
      (node (ref "L6") (pin "P$2") (pinfunction "2_P$2") (pintype "passive"))
      (node (ref "L8") (pin "P$1") (pinfunction "1_P$1") (pintype "passive"))
      (node (ref "U4") (pin "10") (pinfunction "RF_OUT/VCC2_10") (pintype "output"))
      (node (ref "U4") (pin "9") (pinfunction "RF_OUT/VCC2_9") (pintype "output"))
    )
    (net (code "28") (name "Net-(L7-1)") (class "Default")
      (node (ref "C25") (pin "2") (pinfunction "2_2") (pintype "passive"))
      (node (ref "L7") (pin "P$1") (pinfunction "1_P$1") (pintype "passive"))
    )
    (net (code "29") (name "Net-(L7-2)") (class "Default")
      (node (ref "L7") (pin "P$2") (pinfunction "2_P$2") (pintype "passive"))
      (node (ref "U4") (pin "3") (pinfunction "RF_IN_3") (pintype "input"))
    )
    (net (code "30") (name "Net-(Q2-D)") (class "Default")
      (node (ref "Q2") (pin "3") (pinfunction "D_3") (pintype "bidirectional"))
      (node (ref "R9") (pin "1") (pinfunction "1_1") (pintype "passive"))
      (node (ref "U1") (pin "5") (pinfunction "SENSE_5") (pintype "input"))
    )
    (net (code "31") (name "Net-(Q2-G)") (class "Default")
      (node (ref "Q2") (pin "1") (pinfunction "G_1") (pintype "bidirectional"))
      (node (ref "R2") (pin "1") (pinfunction "1_1") (pintype "passive"))
    )
    (net (code "32") (name "Net-(U1-GATE)") (class "Default")
      (node (ref "R11") (pin "1") (pinfunction "1_1") (pintype "passive"))
      (node (ref "R2") (pin "2") (pinfunction "2_2") (pintype "passive"))
      (node (ref "U1") (pin "4") (pinfunction "GATE_4") (pintype "output"))
    )
    (net (code "33") (name "Net-(U1-TIMER)") (class "Default")
      (node (ref "C23") (pin "1") (pinfunction "1_1") (pintype "passive"))
      (node (ref "U1") (pin "1") (pinfunction "TIMER_1") (pintype "input"))
    )
    (net (code "34") (name "Net-(U3-A18VD3)") (class "Default")
      (node (ref "C5") (pin "1") (pinfunction "1_1") (pintype "passive"))
      (node (ref "C6") (pin "1") (pinfunction "1_1") (pintype "passive"))
      (node (ref "L2") (pin "1") (pinfunction "1_1") (pintype "passive"))
      (node (ref "U3") (pin "40") (pinfunction "A18VD3_40") (pintype "power_in"))
    )
    (net (code "35") (name "Net-(U3-A33VD1)") (class "Default")
      (node (ref "C40") (pin "1") (pinfunction "1_1") (pintype "passive"))
      (node (ref "C41") (pin "1") (pinfunction "1_1") (pintype "passive"))
      (node (ref "L15") (pin "1") (pinfunction "1_1") (pintype "passive"))
      (node (ref "U3") (pin "23") (pinfunction "A33VD1_23") (pintype "power_in"))
    )
    (net (code "36") (name "Net-(U3-A33VD2)") (class "Default")
      (node (ref "C7") (pin "1") (pinfunction "1_1") (pintype "passive"))
      (node (ref "C8") (pin "1") (pinfunction "1_1") (pintype "passive"))
      (node (ref "L3") (pin "1") (pinfunction "1_1") (pintype "passive"))
      (node (ref "U3") (pin "36") (pinfunction "A33VD2_36") (pintype "power_in"))
    )
    (net (code "37") (name "Net-(U3-D18VD)") (class "Default")
      (node (ref "C26") (pin "1") (pinfunction "1_1") (pintype "passive"))
      (node (ref "C27") (pin "1") (pinfunction "1_1") (pintype "passive"))
      (node (ref "L9") (pin "1") (pinfunction "1_1") (pintype "passive"))
      (node (ref "U3") (pin "6") (pinfunction "D18VD_6") (pintype "power_in"))
    )
    (net (code "38") (name "Net-(U3-D33VD)") (class "Default")
      (node (ref "C32") (pin "1") (pinfunction "1_1") (pintype "passive"))
      (node (ref "C33") (pin "1") (pinfunction "1_1") (pintype "passive"))
      (node (ref "L10") (pin "1") (pinfunction "1_1") (pintype "passive"))
      (node (ref "R5") (pin "2") (pinfunction "2_2") (pintype "passive"))
      (node (ref "R8") (pin "1") (pinfunction "1_1") (pintype "passive"))
      (node (ref "U3") (pin "9") (pinfunction "D33VD_9") (pintype "power_in"))
    )
    (net (code "39") (name "Net-(U3-FREF)") (class "Default")
      (node (ref "C17") (pin "2") (pinfunction "2_2") (pintype "passive"))
      (node (ref "U3") (pin "38") (pinfunction "FREF_38") (pintype "bidirectional"))
    )
    (net (code "40") (name "Net-(U3-FREFVD)") (class "Default")
      (node (ref "C10") (pin "1") (pinfunction "1_1") (pintype "passive"))
      (node (ref "C9") (pin "1") (pinfunction "1_1") (pintype "passive"))
      (node (ref "U3") (pin "37") (pinfunction "FREFVD_37") (pintype "bidirectional"))
      (node (ref "X1") (pin "4") (pinfunction "VCC_4") (pintype "bidirectional"))
    )
    (net (code "41") (name "Net-(U3-RBIAS)") (class "Default")
      (node (ref "R4") (pin "1") (pinfunction "1_1") (pintype "passive"))
      (node (ref "U3") (pin "41") (pinfunction "RBIAS_41") (pintype "bidirectional"))
    )
    (net (code "42") (name "Net-(U3-TXOUT)") (class "Default")
      (node (ref "C24") (pin "1") (pinfunction "1_1") (pintype "passive"))
      (node (ref "U3") (pin "34") (pinfunction "TXOUT_34") (pintype "bidirectional"))
    )
    (net (code "43") (name "Net-(U4-G16)") (class "Default")
      (node (ref "C47") (pin "2") (pinfunction "2_2") (pintype "passive"))
      (node (ref "G16") (pin "1") (pinfunction "1_1") (pintype "passive"))
      (node (ref "R1") (pin "1") (pinfunction "1_1") (pintype "passive"))
      (node (ref "U4") (pin "13") (pinfunction "G16_13") (pintype "input"))
    )
    (net (code "44") (name "Net-(U4-PD)") (class "Default")
      (node (ref "C43") (pin "2") (pinfunction "2_2") (pintype "passive"))
      (node (ref "C44") (pin "1") (pinfunction "1_1") (pintype "passive"))
      (node (ref "R14") (pin "2") (pinfunction "2_2") (pintype "passive"))
      (node (ref "R17") (pin "2") (pinfunction "2_2") (pintype "passive"))
      (node (ref "U4") (pin "6") (pinfunction "PD_6") (pintype "input"))
    )
    (net (code "45") (name "Net-(U5-J1)") (class "Default")
      (node (ref "C37") (pin "2") (pinfunction "2_2") (pintype "passive"))
      (node (ref "U5") (pin "5") (pinfunction "J1_5") (pintype "bidirectional"))
    )
    (net (code "46") (name "Net-(U5-J2)") (class "Default")
      (node (ref "C30") (pin "1") (pinfunction "1_1") (pintype "passive"))
      (node (ref "U5") (pin "3") (pinfunction "J2_3") (pintype "bidirectional"))
    )
    (net (code "47") (name "Net-(U5-J3)") (class "Default")
      (node (ref "C31") (pin "1") (pinfunction "1_1") (pintype "passive"))
      (node (ref "U5") (pin "1") (pinfunction "J3_1") (pintype "bidirectional"))
    )
    (net (code "48") (name "Net-(U7-HOLD)") (class "Default")
      (node (ref "C50") (pin "1") (pinfunction "1_1") (pintype "passive"))
      (node (ref "L1") (pin "1") (pinfunction "1_1") (pintype "passive"))
      (node (ref "U7") (pin "3") (pinfunction "WP_3") (pintype "bidirectional"))
      (node (ref "U7") (pin "7") (pinfunction "HOLD_7") (pintype "bidirectional"))
      (node (ref "U7") (pin "8") (pinfunction "VCC_8") (pintype "power_in"))
    )
    (net (code "49") (name "Net-(X1-OUT)") (class "Default")
      (node (ref "C17") (pin "1") (pinfunction "1_1") (pintype "passive"))
      (node (ref "X1") (pin "3") (pinfunction "OUT_3") (pintype "bidirectional"))
    )
    (net (code "50") (name "PA_PD") (class "Default")
      (node (ref "R17") (pin "1") (pinfunction "1_1") (pintype "passive"))
      (node (ref "U3") (pin "7") (pinfunction "GPIO7_7") (pintype "bidirectional"))
    )
    (net (code "51") (name "PROC_PWR_EN") (class "Default")
      (node (ref "IN") (pin "1") (pinfunction "1_1") (pintype "passive"))
      (node (ref "OUT") (pin "1") (pinfunction "1_1") (pintype "passive"))
    )
    (net (code "52") (name "RESETB") (class "Default")
      (node (ref "R8") (pin "2") (pinfunction "2_2") (pintype "passive"))
      (node (ref "U3") (pin "1") (pinfunction "RESETB_1") (pintype "bidirectional"))
      (node (ref "U8") (pin "1") (pinfunction "GPIO0_1") (pintype "bidirectional"))
    )
    (net (code "53") (name "RFG8") (class "Default")
      (node (ref "C22") (pin "2") (pinfunction "2_2") (pintype "passive"))
      (node (ref "K1") (pin "4") (pinfunction "DRAIN_2_4") (pintype "bidirectional"))
      (node (ref "R7") (pin "1") (pinfunction "1_1") (pintype "passive"))
      (node (ref "U4") (pin "12") (pinfunction "G8_12") (pintype "input"))
    )
    (net (code "54") (name "RF_RX") (class "Default")
      (node (ref "C29") (pin "P$2") (pinfunction "2_P$2") (pintype "passive"))
      (node (ref "C30") (pin "2") (pinfunction "2_2") (pintype "passive"))
      (node (ref "L12") (pin "P$2") (pinfunction "2_P$2") (pintype "passive"))
    )
    (net (code "55") (name "RF_TX") (class "Default")
      (node (ref "C28") (pin "2") (pinfunction "2_2") (pintype "passive"))
      (node (ref "C31") (pin "2") (pinfunction "2_2") (pintype "passive"))
      (node (ref "L8") (pin "P$2") (pinfunction "2_P$2") (pintype "passive"))
    )
    (net (code "56") (name "RXSW") (class "Default")
      (node (ref "C36") (pin "1") (pinfunction "1_1") (pintype "passive"))
      (node (ref "U3") (pin "22") (pinfunction "RXSW_22") (pintype "bidirectional"))
      (node (ref "U5") (pin "6") (pinfunction "V2_6") (pintype "power_in"))
    )
    (net (code "57") (name "SCL") (class "Default")
      (node (ref "IN") (pin "13") (pinfunction "13_13") (pintype "passive"))
      (node (ref "OUT") (pin "13") (pinfunction "13_13") (pintype "passive"))
      (node (ref "U8") (pin "6") (pinfunction "SCL_6") (pintype "bidirectional"))
    )
    (net (code "58") (name "SCLK") (class "Default")
      (node (ref "IN") (pin "4") (pinfunction "4_4") (pintype "passive"))
      (node (ref "OUT") (pin "4") (pinfunction "4_4") (pintype "passive"))
      (node (ref "U3") (pin "3") (pinfunction "SCLK_3") (pintype "bidirectional"))
    )
    (net (code "59") (name "SDA") (class "Default")
      (node (ref "IN") (pin "12") (pinfunction "12_12") (pintype "passive"))
      (node (ref "OUT") (pin "12") (pinfunction "12_12") (pintype "passive"))
      (node (ref "U8") (pin "7") (pinfunction "SDA_7") (pintype "bidirectional"))
    )
    (net (code "60") (name "TXSW") (class "Default")
      (node (ref "C42") (pin "1") (pinfunction "1_1") (pintype "passive"))
      (node (ref "U3") (pin "21") (pinfunction "TXSW_21") (pintype "bidirectional"))
      (node (ref "U5") (pin "4") (pinfunction "V1_4") (pintype "power_in"))
    )
    (net (code "61") (name "VDD") (class "Default")
      (node (ref "C14") (pin "1") (pinfunction "1_1") (pintype "passive"))
      (node (ref "C16") (pin "1") (pinfunction "1_1") (pintype "passive"))
      (node (ref "C19") (pin "1") (pinfunction "1_1") (pintype "passive"))
      (node (ref "C3") (pin "1") (pinfunction "1_1") (pintype "passive"))
      (node (ref "C45") (pin "1") (pinfunction "1_1") (pintype "passive"))
      (node (ref "C46") (pin "1") (pinfunction "1_1") (pintype "passive"))
      (node (ref "C49") (pin "1") (pinfunction "1_1") (pintype "passive"))
      (node (ref "C51") (pin "1") (pinfunction "1_1") (pintype "passive"))
      (node (ref "L1") (pin "2") (pinfunction "2_2") (pintype "passive"))
      (node (ref "L10") (pin "2") (pinfunction "2_2") (pintype "passive"))
      (node (ref "L15") (pin "2") (pinfunction "2_2") (pintype "passive"))
      (node (ref "L3") (pin "2") (pinfunction "2_2") (pintype "passive"))
      (node (ref "L6") (pin "P$1") (pinfunction "1_P$1") (pintype "passive"))
      (node (ref "Q2") (pin "2") (pinfunction "S_2") (pintype "bidirectional"))
      (node (ref "R3") (pin "2") (pinfunction "2_2") (pintype "passive"))
      (node (ref "U2") (pin "1") (pinfunction "IN_1") (pintype "input"))
      (node (ref "U2") (pin "3") (pinfunction "EN_3") (pintype "input"))
      (node (ref "U6") (pin "1") (pinfunction "IN_1") (pintype "input"))
      (node (ref "U6") (pin "3") (pinfunction "EN_3") (pintype "input"))
      (node (ref "U8") (pin "8") (pinfunction "VCC_8") (pintype "bidirectional"))
      (node (ref "VDD") (pin "1") (pinfunction "1_1") (pintype "bidirectional"))
    )
    (net (code "62") (name "VREF1") (class "Default")
      (node (ref "3V0") (pin "1") (pinfunction "1_1") (pintype "bidirectional"))
      (node (ref "C20") (pin "2") (pinfunction "2_2") (pintype "passive"))
      (node (ref "C21") (pin "2") (pinfunction "2_2") (pintype "passive"))
      (node (ref "G16") (pin "2") (pinfunction "2_2") (pintype "passive"))
      (node (ref "K1") (pin "3") (pinfunction "DRAIN_1_3") (pintype "bidirectional"))
      (node (ref "U4") (pin "16") (pinfunction "VBIAS_16") (pintype "power_in"))
      (node (ref "U6") (pin "5") (pinfunction "OUT_5") (pintype "passive"))
    )
    (net (code "63") (name "V_USB") (class "Default")
      (node (ref "IN") (pin "16") (pinfunction "16_16") (pintype "passive"))
      (node (ref "OUT") (pin "16") (pinfunction "16_16") (pintype "passive"))
    )
    (net (code "64") (name "unconnected-(OUT-Pad9)") (class "Default")
      (node (ref "OUT") (pin "9") (pinfunction "9_9") (pintype "passive"))
    )
    (net (code "65") (name "unconnected-(OUT-Pad11)") (class "Default")
      (node (ref "OUT") (pin "11") (pinfunction "11_11") (pintype "passive"))
    )
    (net (code "66") (name "unconnected-(U2-NC-Pad4)") (class "Default")
      (node (ref "U2") (pin "4") (pinfunction "NC_4") (pintype "no_connect"))
    )
    (net (code "67") (name "unconnected-(U3-GPIO0-Pad19)") (class "Default")
      (node (ref "U3") (pin "19") (pinfunction "GPIO0_19") (pintype "bidirectional"))
    )
    (net (code "68") (name "unconnected-(U3-GPIO1-Pad18)") (class "Default")
      (node (ref "U3") (pin "18") (pinfunction "GPIO1_18") (pintype "bidirectional"))
    )
    (net (code "69") (name "unconnected-(U3-GPIO2-Pad17)") (class "Default")
      (node (ref "U3") (pin "17") (pinfunction "GPIO2_17") (pintype "bidirectional"))
    )
    (net (code "70") (name "unconnected-(U3-GPIO3-Pad16)") (class "Default")
      (node (ref "U3") (pin "16") (pinfunction "GPIO3_16") (pintype "bidirectional"))
    )
    (net (code "71") (name "unconnected-(U3-GPIO4-Pad11)") (class "Default")
      (node (ref "U3") (pin "11") (pinfunction "GPIO4_11") (pintype "bidirectional"))
    )
    (net (code "72") (name "unconnected-(U3-GPIO5-Pad10)") (class "Default")
      (node (ref "U3") (pin "10") (pinfunction "GPIO5_10") (pintype "bidirectional"))
    )
    (net (code "73") (name "unconnected-(U3-GPIO6-Pad8)") (class "Default")
      (node (ref "U3") (pin "8") (pinfunction "GPIO6_8") (pintype "bidirectional"))
    )
    (net (code "74") (name "unconnected-(U3-INT2-Pad48)") (class "Default")
      (node (ref "U3") (pin "48") (pinfunction "INT2_48") (pintype "bidirectional"))
    )
    (net (code "75") (name "unconnected-(U3-NC-Pad42)") (class "Default")
      (node (ref "U3") (pin "42") (pinfunction "NC_42") (pintype "no_connect"))
    )
    (net (code "76") (name "unconnected-(U3-NC-Pad43)") (class "Default")
      (node (ref "U3") (pin "43") (pinfunction "NC_43") (pintype "no_connect"))
    )
    (net (code "77") (name "unconnected-(U3-NC-Pad44)") (class "Default")
      (node (ref "U3") (pin "44") (pinfunction "NC_44") (pintype "no_connect"))
    )
    (net (code "78") (name "unconnected-(U3-NC-Pad45)") (class "Default")
      (node (ref "U3") (pin "45") (pinfunction "NC_45") (pintype "no_connect"))
    )
    (net (code "79") (name "unconnected-(U4-NC-Pad1)") (class "Default")
      (node (ref "U4") (pin "1") (pinfunction "NC_1") (pintype "no_connect"))
    )
    (net (code "80") (name "unconnected-(U4-NC-Pad4)") (class "Default")
      (node (ref "U4") (pin "4") (pinfunction "NC_4") (pintype "no_connect"))
    )
    (net (code "81") (name "unconnected-(U4-NC-Pad5)") (class "Default")
      (node (ref "U4") (pin "5") (pinfunction "NC_5") (pintype "no_connect"))
    )
    (net (code "82") (name "unconnected-(U4-NC-Pad7)") (class "Default")
      (node (ref "U4") (pin "7") (pinfunction "NC_7") (pintype "no_connect"))
    )
    (net (code "83") (name "unconnected-(U4-NC-Pad8)") (class "Default")
      (node (ref "U4") (pin "8") (pinfunction "NC_8") (pintype "no_connect"))
    )
    (net (code "84") (name "unconnected-(U4-NC-Pad11)") (class "Default")
      (node (ref "U4") (pin "11") (pinfunction "NC_11") (pintype "no_connect"))
    )
    (net (code "85") (name "unconnected-(U4-NC-Pad15)") (class "Default")
      (node (ref "U4") (pin "15") (pinfunction "NC_15") (pintype "no_connect"))
    )
    (net (code "86") (name "unconnected-(U6-NC-Pad4)") (class "Default")
      (node (ref "U6") (pin "4") (pinfunction "NC_4") (pintype "no_connect"))
    )
  )
)
